# Top.net
KiCad netlist of a schematic drawn in Altium Designer
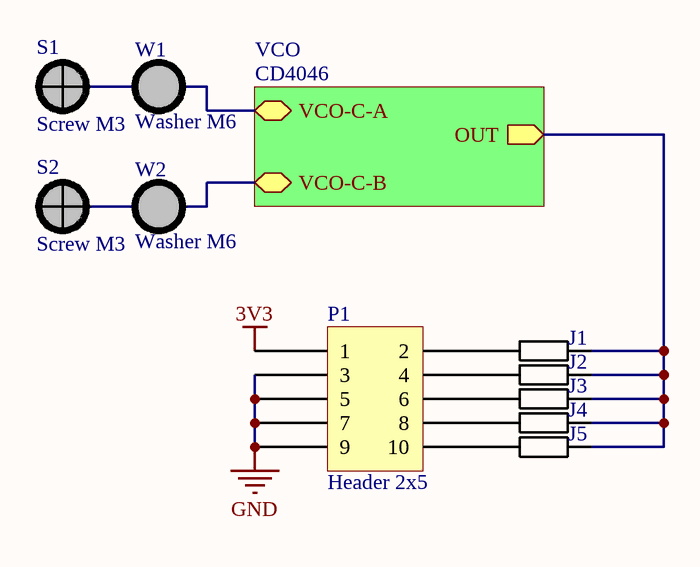
[diagram p0: Top.SchDoc]

(export (version "E")
  (design (tool "Eeschema 10.0.6"))
  (components
    (comp (ref "J1")
      (value "~")
      (footprint "R 0805 / 2012 wide")
      (libsource (lib "Standard") (part "Resistor"))
    )
    (comp (ref "J2")
      (value "~")
      (footprint "R 0805 / 2012 wide")
      (libsource (lib "Standard") (part "Resistor"))
    )
    (comp (ref "J3")
      (value "~")
      (footprint "R 0805 / 2012 wide")
      (libsource (lib "Standard") (part "Resistor"))
    )
    (comp (ref "J4")
      (value "~")
      (footprint "R 0805 / 2012 wide")
      (libsource (lib "Standard") (part "Resistor"))
    )
    (comp (ref "J5")
      (value "~")
      (footprint "R 0805 / 2012 wide")
      (libsource (lib "Standard") (part "Resistor"))
    )
    (comp (ref "P1")
      (value "Header 2x5")
      (footprint "Header 2x5 IDC-10S")
      (libsource (lib "Headers") (part "Header 2x5"))
    )
    (comp (ref "S1")
      (value "Screw M3")
      (footprint "Screw M3")
      (libsource (lib "Mechanical") (part "Screw M3"))
    )
    (comp (ref "S2")
      (value "Screw M3")
      (footprint "Screw M3")
      (libsource (lib "Mechanical") (part "Screw M3"))
    )
    (comp (ref "W1")
      (value "Washer M6")
      (footprint "Washer M6")
      (libsource (lib "Mechanical") (part "Washer M6"))
    )
    (comp (ref "W2")
      (value "Washer M6")
      (footprint "Washer M6")
      (libsource (lib "Mechanical") (part "Washer M6"))
    )
  )
  (nets
    (net (code "1") (name "/OUT") (class "Default")
      (node (ref "J1") (pin "2") (pinfunction "2_2") (pintype "passive"))
      (node (ref "J2") (pin "2") (pinfunction "2_2") (pintype "passive"))
      (node (ref "J3") (pin "2") (pinfunction "2_2") (pintype "passive"))
      (node (ref "J4") (pin "2") (pinfunction "2_2") (pintype "passive"))
      (node (ref "J5") (pin "2") (pinfunction "2_2") (pintype "passive"))
    )
    (net (code "4") (name "3V3") (class "Default")
      (node (ref "P1") (pin "1") (pinfunction "1_1") (pintype "passive"))
    )
    (net (code "5") (name "GND") (class "Default")
      (node (ref "P1") (pin "3") (pinfunction "3_3") (pintype "passive"))
      (node (ref "P1") (pin "5") (pinfunction "5_5") (pintype "passive"))
      (node (ref "P1") (pin "7") (pinfunction "7_7") (pintype "passive"))
      (node (ref "P1") (pin "9") (pinfunction "9_9") (pintype "passive"))
    )
    (net (code "6") (name "Net-(J1-Pad1)") (class "Default")
      (node (ref "J1") (pin "1") (pinfunction "1_1") (pintype "passive"))
      (node (ref "P1") (pin "2") (pinfunction "2_2") (pintype "passive"))
    )
    (net (code "7") (name "Net-(J2-Pad1)") (class "Default")
      (node (ref "J2") (pin "1") (pinfunction "1_1") (pintype "passive"))
      (node (ref "P1") (pin "4") (pinfunction "4_4") (pintype "passive"))
    )
    (net (code "8") (name "Net-(J3-Pad1)") (class "Default")
      (node (ref "J3") (pin "1") (pinfunction "1_1") (pintype "passive"))
      (node (ref "P1") (pin "6") (pinfunction "6_6") (pintype "passive"))
    )
    (net (code "9") (name "Net-(J4-Pad1)") (class "Default")
      (node (ref "J4") (pin "1") (pinfunction "1_1") (pintype "passive"))
      (node (ref "P1") (pin "8") (pinfunction "8_8") (pintype "passive"))
    )
    (net (code "10") (name "Net-(J5-Pad1)") (class "Default")
      (node (ref "J5") (pin "1") (pinfunction "1_1") (pintype "passive"))
      (node (ref "P1") (pin "10") (pinfunction "10_10") (pintype "passive"))
    )
  )
)
